# LCD.net
KiCad netlist of a schematic drawn in Altium Designer
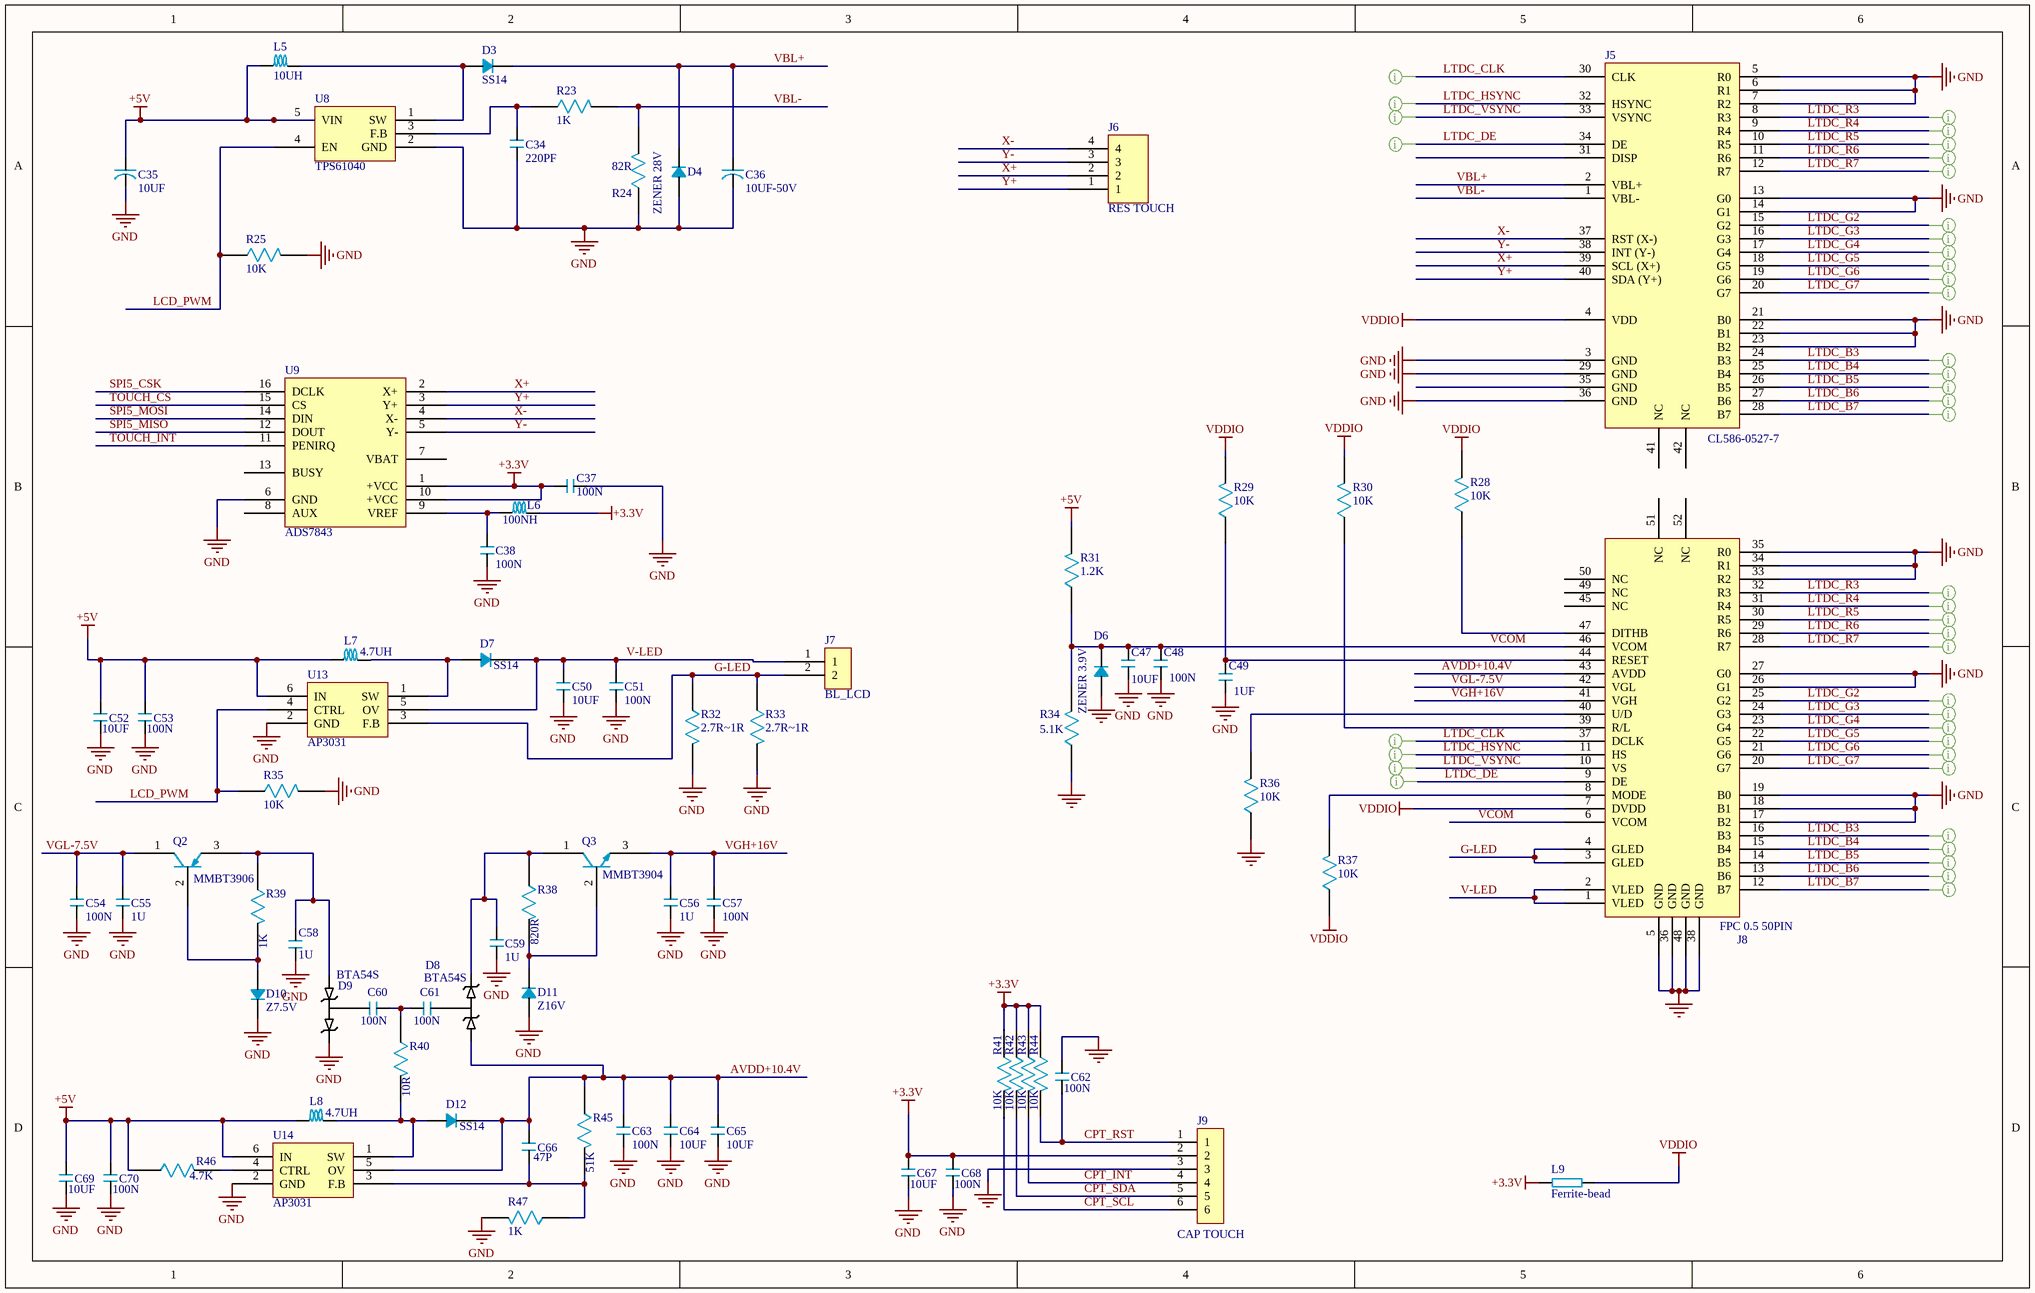
[diagram p0: LCD.SchDoc]

(export (version "E")
  (design (tool "Eeschema 10.0.6"))
  (components
    (comp (ref "C34") (value "220PF") (footprint "1206") (libsource (lib "R_L_C_V") (part "CAP")))
    (comp (ref "C35") (value "10UF") (footprint "1206") (libsource (lib "R_L_C_V") (part "CAP_POL")))
    (comp (ref "C36") (value "10UF-50V") (footprint "RB.1/.3") (libsource (lib "R_L_C_V") (part "CAP_POL")))
    (comp (ref "C37") (value "100N") (footprint "0603") (libsource (lib "R_L_C_V") (part "CAP")))
    (comp (ref "C38") (value "100N") (footprint "0603") (libsource (lib "R_L_C_V") (part "CAP")))
    (comp (ref "C47") (value "10UF") (footprint "0603") (libsource (lib "R_L_C_V") (part "CAP")))
    (comp (ref "C48") (value "100N") (footprint "0603") (libsource (lib "R_L_C_V") (part "CAP")))
    (comp (ref "C49") (value "1UF") (footprint "0603") (libsource (lib "R_L_C_V") (part "CAP")))
    (comp (ref "C50") (value "10UF") (footprint "0603") (libsource (lib "R_L_C_V") (part "CAP")))
    (comp (ref "C51") (value "100N") (footprint "0603") (libsource (lib "R_L_C_V") (part "CAP")))
    (comp (ref "C52") (value "10UF") (footprint "0603") (libsource (lib "R_L_C_V") (part "CAP")))
    (comp (ref "C53") (value "100N") (footprint "0603") (libsource (lib "R_L_C_V") (part "CAP")))
    (comp (ref "C54") (value "100N") (footprint "0603") (libsource (lib "R_L_C_V") (part "CAP")))
    (comp (ref "C55") (value "1U") (footprint "0603") (libsource (lib "R_L_C_V") (part "CAP")))
    (comp (ref "C56") (value "1U") (footprint "0603") (libsource (lib "R_L_C_V") (part "CAP")))
    (comp (ref "C57") (value "100N") (footprint "0603") (libsource (lib "R_L_C_V") (part "CAP")))
    (comp (ref "C58") (value "1U") (footprint "0603") (libsource (lib "R_L_C_V") (part "CAP")))
    (comp (ref "C59") (value "1U") (footprint "0603") (libsource (lib "R_L_C_V") (part "CAP")))
    (comp (ref "C60") (value "100N") (footprint "0603") (libsource (lib "R_L_C_V") (part "CAP")))
    (comp (ref "C61") (value "100N") (footprint "0603") (libsource (lib "R_L_C_V") (part "CAP")))
    (comp (ref "C62") (value "100N") (footprint "0603") (libsource (lib "R_L_C_V") (part "CAP")))
    (comp (ref "C63") (value "100N") (footprint "0603") (libsource (lib "R_L_C_V") (part "CAP")))
    (comp (ref "C64") (value "10UF") (footprint "0603") (libsource (lib "R_L_C_V") (part "CAP")))
    (comp (ref "C65") (value "10UF") (footprint "0603") (libsource (lib "R_L_C_V") (part "CAP")))
    (comp (ref "C66") (value "47P") (footprint "0603") (libsource (lib "R_L_C_V") (part "CAP")))
    (comp (ref "C67") (value "10UF") (footprint "0603") (libsource (lib "R_L_C_V") (part "CAP")))
    (comp (ref "C68") (value "100N") (footprint "0603") (libsource (lib "R_L_C_V") (part "CAP")))
    (comp (ref "C69") (value "10UF") (footprint "0603") (libsource (lib "R_L_C_V") (part "CAP")))
    (comp (ref "C70") (value "100N") (footprint "0603") (libsource (lib "R_L_C_V") (part "CAP")))
    (comp (ref "D3") (value "SS14") (footprint "SOD-123-B") (libsource (lib "R_L_C_V") (part "DIODE")))
    (comp (ref "D4") (value "ZENER 28V") (footprint "SOD-123") (libsource (lib "R_L_C_V") (part "DIODE")))
    (comp (ref "D6") (value "ZENER 3.9V") (footprint "SOD-123") (libsource (lib "R_L_C_V") (part "DIODE")))
    (comp (ref "D7") (value "SS14") (footprint "SOD-123-B") (libsource (lib "R_L_C_V") (part "DIODE")))
    (comp (ref "D8") (value "BTA54S") (footprint "SOT-23") (libsource (lib "MY_IC") (part "BTA54S")))
    (comp (ref "D9") (value "BTA54S") (footprint "SOT-23") (libsource (lib "MY_IC") (part "BTA54S")))
    (comp (ref "D10") (value "Z7.5V") (footprint "MINI-MELF") (libsource (lib "R_L_C_V") (part "DIODE")))
    (comp (ref "D11") (value "Z16V") (footprint "MINI-MELF") (libsource (lib "R_L_C_V") (part "DIODE")))
    (comp (ref "D12") (value "SS14") (footprint "SOD-123-B") (libsource (lib "R_L_C_V") (part "DIODE")))
    (comp (ref "J5")
      (value "CL586-0527-7")
      (footprint "PFC-40")
      (libsource (lib "CONNECTOR") (part "FPC 0.5 40PIN"))
    )
    (comp (ref "J6")
      (value "RES TOUCH")
      (footprint "4PIN-1.5MM-SMD")
      (libsource (lib "CONNECTOR") (part "4-PIN"))
    )
    (comp (ref "J7") (value "BL_LCD") (footprint "BL_LCD") (libsource (lib "CONNECTOR") (part "BL_LCD")))
    (comp (ref "J8")
      (value "FPC 0.5 50PIN")
      (footprint "PFC-50")
      (libsource (lib "CONNECTOR") (part "FPC 0.5 50PIN"))
    )
    (comp (ref "J9")
      (value "CAP TOUCH")
      (footprint "FPC-6-TOP-1MM")
      (description "FPC-6-TOP-1MM")
      (libsource (lib "CONNECTOR") (part "FPC-6-TOP-1MM"))
    )
    (comp (ref "L5") (value "10UH") (footprint "SELF_7MM") (libsource (lib "R_L_C_V") (part "SELF")))
    (comp (ref "L6") (value "100NH") (footprint "1206") (libsource (lib "R_L_C_V") (part "SELF")))
    (comp (ref "L7") (value "4.7UH") (footprint "SELF_7MM") (libsource (lib "R_L_C_V") (part "SELF")))
    (comp (ref "L8") (value "4.7UH") (footprint "SELF_7MM") (libsource (lib "") (part "SELF_1")))
    (comp (ref "L9")
      (value "Ferrite-bead")
      (footprint "0805")
      (libsource (lib "My_lib") (part "Ferrite-bead"))
    )
    (comp (ref "Q2") (value "MMBT3906") (footprint "BC337") (libsource (lib "TRANSISTORS") (part "PNP-SMD")))
    (comp (ref "Q3") (value "MMBT3904") (footprint "BC337") (libsource (lib "TRANSISTORS") (part "NPN-SMD")))
    (comp (ref "R23")
      (value "1K")
      (footprint "1206")
      (description "RES")
      (libsource (lib "R_L_C_V") (part "RES"))
    )
    (comp (ref "R24")
      (value "82R")
      (footprint "1206")
      (description "RES")
      (libsource (lib "R_L_C_V") (part "RES"))
    )
    (comp (ref "R25")
      (value "10K")
      (footprint "1206")
      (description "RES")
      (libsource (lib "R_L_C_V") (part "RES"))
    )
    (comp (ref "R28")
      (value "10K")
      (footprint "0603")
      (description "RES")
      (libsource (lib "R_L_C_V") (part "RES"))
    )
    (comp (ref "R29")
      (value "10K")
      (footprint "0603")
      (description "RES")
      (libsource (lib "R_L_C_V") (part "RES"))
    )
    (comp (ref "R30")
      (value "10K")
      (footprint "0603")
      (description "RES")
      (libsource (lib "R_L_C_V") (part "RES"))
    )
    (comp (ref "R31")
      (value "1.2K")
      (footprint "0603")
      (description "RES")
      (libsource (lib "R_L_C_V") (part "RES"))
    )
    (comp (ref "R32")
      (value "2.7R~1R")
      (footprint "0603")
      (description "RES")
      (libsource (lib "R_L_C_V") (part "RES"))
    )
    (comp (ref "R33")
      (value "2.7R~1R")
      (footprint "0603")
      (description "RES")
      (libsource (lib "R_L_C_V") (part "RES"))
    )
    (comp (ref "R34")
      (value "5.1K")
      (footprint "0603")
      (description "RES")
      (libsource (lib "R_L_C_V") (part "RES"))
    )
    (comp (ref "R35")
      (value "10K")
      (footprint "0603")
      (description "RES")
      (libsource (lib "R_L_C_V") (part "RES"))
    )
    (comp (ref "R36")
      (value "10K")
      (footprint "0603")
      (description "RES")
      (libsource (lib "R_L_C_V") (part "RES"))
    )
    (comp (ref "R37")
      (value "10K")
      (footprint "0603")
      (description "RES")
      (libsource (lib "R_L_C_V") (part "RES"))
    )
    (comp (ref "R38")
      (value "820R")
      (footprint "0603")
      (description "RES")
      (libsource (lib "R_L_C_V") (part "RES"))
    )
    (comp (ref "R39")
      (value "1K")
      (footprint "0603")
      (description "RES")
      (libsource (lib "R_L_C_V") (part "RES"))
    )
    (comp (ref "R40")
      (value "10R")
      (footprint "0603")
      (description "RES")
      (libsource (lib "R_L_C_V") (part "RES"))
    )
    (comp (ref "R41")
      (value "10K")
      (footprint "0603")
      (description "RES")
      (libsource (lib "R_L_C_V") (part "RES"))
    )
    (comp (ref "R42")
      (value "10K")
      (footprint "0603")
      (description "RES")
      (libsource (lib "R_L_C_V") (part "RES"))
    )
    (comp (ref "R43")
      (value "10K")
      (footprint "0603")
      (description "RES")
      (libsource (lib "R_L_C_V") (part "RES"))
    )
    (comp (ref "R44")
      (value "10K")
      (footprint "0603")
      (description "RES")
      (libsource (lib "R_L_C_V") (part "RES"))
    )
    (comp (ref "R45")
      (value "51K")
      (footprint "0603")
      (description "RES")
      (libsource (lib "R_L_C_V") (part "RES"))
    )
    (comp (ref "R46")
      (value "4.7K")
      (footprint "0603")
      (description "RES")
      (libsource (lib "R_L_C_V") (part "RES"))
    )
    (comp (ref "R47")
      (value "1K")
      (footprint "0603")
      (description "RES")
      (libsource (lib "R_L_C_V") (part "RES"))
    )
    (comp (ref "U8") (value "TPS61040") (footprint "SOT23-5") (libsource (lib "MY_IC") (part "TPS61040")))
    (comp (ref "U9") (value "ADS7843") (footprint "TSSOP-16") (libsource (lib "MY_IC") (part "ADS7843")))
    (comp (ref "U13") (value "AP3031") (footprint "SOT23-6") (libsource (lib "MY_IC") (part "AP3031")))
    (comp (ref "U14") (value "AP3031") (footprint "SOT23-6") (libsource (lib "MY_IC") (part "AP3031")))
  )
  (nets
    (net (code "1") (name "+3.3V") (class "Default")
      (node (ref "C37") (pin "2") (pintype "passive"))
      (node (ref "C67") (pin "1") (pintype "passive"))
      (node (ref "C68") (pin "1") (pintype "passive"))
      (node (ref "J9") (pin "2") (pinfunction "2_2") (pintype "passive"))
      (node (ref "L6") (pin "2") (pintype "passive"))
      (node (ref "L9") (pin "1") (pintype "passive"))
      (node (ref "R41") (pin "1") (pintype "passive"))
      (node (ref "R42") (pin "1") (pintype "passive"))
      (node (ref "R43") (pin "1") (pintype "passive"))
      (node (ref "R44") (pin "1") (pintype "passive"))
      (node (ref "U9") (pin "1") (pinfunction "+VCC_1") (pintype "passive"))
      (node (ref "U9") (pin "10") (pinfunction "+VCC_10") (pintype "passive"))
    )
    (net (code "2") (name "+5V") (class "Default")
      (node (ref "C35") (pin "1") (pintype "passive"))
      (node (ref "C52") (pin "1") (pintype "passive"))
      (node (ref "C53") (pin "1") (pintype "passive"))
      (node (ref "C69") (pin "1") (pintype "passive"))
      (node (ref "C70") (pin "1") (pintype "passive"))
      (node (ref "L5") (pin "1") (pintype "passive"))
      (node (ref "L7") (pin "1") (pintype "passive"))
      (node (ref "L8") (pin "1") (pintype "passive"))
      (node (ref "R31") (pin "2") (pintype "passive"))
      (node (ref "R46") (pin "1") (pintype "passive"))
      (node (ref "U13") (pin "6") (pinfunction "IN_6") (pintype "passive"))
      (node (ref "U14") (pin "6") (pinfunction "IN_6") (pintype "passive"))
      (node (ref "U8") (pin "5") (pinfunction "VIN_5") (pintype "passive"))
    )
    (net (code "3") (name "/AVDD+10.4V") (class "Default")
      (node (ref "C63") (pin "1") (pintype "passive"))
      (node (ref "C64") (pin "1") (pintype "passive"))
      (node (ref "C65") (pin "1") (pintype "passive"))
      (node (ref "C66") (pin "1") (pintype "passive"))
      (node (ref "D12") (pin "2") (pintype "passive"))
      (node (ref "D8") (pin "1") (pinfunction "1_1") (pintype "passive"))
      (node (ref "J8") (pin "43") (pinfunction "AVDD_43") (pintype "passive"))
      (node (ref "R45") (pin "1") (pintype "passive"))
      (node (ref "U14") (pin "5") (pinfunction "OV_5") (pintype "passive"))
    )
    (net (code "4") (name "/CPT_INT") (class "Default")
      (node (ref "J9") (pin "4") (pinfunction "4_4") (pintype "passive"))
      (node (ref "R43") (pin "2") (pintype "passive"))
    )
    (net (code "5") (name "/CPT_RST") (class "Default")
      (node (ref "C62") (pin "2") (pintype "passive"))
      (node (ref "J9") (pin "1") (pinfunction "1_1") (pintype "passive"))
      (node (ref "R44") (pin "2") (pintype "passive"))
    )
    (net (code "6") (name "/CPT_SCL") (class "Default")
      (node (ref "J9") (pin "6") (pinfunction "6_6") (pintype "passive"))
      (node (ref "R41") (pin "2") (pintype "passive"))
    )
    (net (code "7") (name "/CPT_SDA") (class "Default")
      (node (ref "J9") (pin "5") (pinfunction "5_5") (pintype "passive"))
      (node (ref "R42") (pin "2") (pintype "passive"))
    )
    (net (code "8") (name "/G-LED") (class "Default")
      (node (ref "J7") (pin "2") (pinfunction "2_2") (pintype "passive"))
      (node (ref "J8") (pin "3") (pinfunction "GLED_3") (pintype "passive"))
      (node (ref "J8") (pin "4") (pinfunction "GLED_4") (pintype "passive"))
      (node (ref "R32") (pin "1") (pintype "passive"))
      (node (ref "R33") (pin "1") (pintype "passive"))
      (node (ref "U13") (pin "3") (pinfunction "F.B_3") (pintype "passive"))
    )
    (net (code "9") (name "/LCD_PWM") (class "Default")
      (node (ref "R25") (pin "1") (pintype "passive"))
      (node (ref "R35") (pin "1") (pintype "passive"))
      (node (ref "U13") (pin "4") (pinfunction "CTRL_4") (pintype "passive"))
      (node (ref "U8") (pin "4") (pinfunction "EN_4") (pintype "passive"))
    )
    (net (code "10") (name "/LTDC_B3") (class "Default")
      (node (ref "J5") (pin "24") (pinfunction "B3_24") (pintype "passive"))
      (node (ref "J8") (pin "16") (pinfunction "B3_16") (pintype "passive"))
    )
    (net (code "11") (name "/LTDC_B4") (class "Default")
      (node (ref "J5") (pin "25") (pinfunction "B4_25") (pintype "passive"))
      (node (ref "J8") (pin "15") (pinfunction "B4_15") (pintype "passive"))
    )
    (net (code "12") (name "/LTDC_B5") (class "Default")
      (node (ref "J5") (pin "26") (pinfunction "B5_26") (pintype "passive"))
      (node (ref "J8") (pin "14") (pinfunction "B5_14") (pintype "passive"))
    )
    (net (code "13") (name "/LTDC_B6") (class "Default")
      (node (ref "J5") (pin "27") (pinfunction "B6_27") (pintype "passive"))
      (node (ref "J8") (pin "13") (pinfunction "B6_13") (pintype "passive"))
    )
    (net (code "14") (name "/LTDC_B7") (class "Default")
      (node (ref "J5") (pin "28") (pinfunction "B7_28") (pintype "passive"))
      (node (ref "J8") (pin "12") (pinfunction "B7_12") (pintype "passive"))
    )
    (net (code "15") (name "/LTDC_CLK") (class "Default")
      (node (ref "J5") (pin "30") (pinfunction "CLK_30") (pintype "passive"))
      (node (ref "J8") (pin "37") (pinfunction "DCLK_37") (pintype "passive"))
    )
    (net (code "16") (name "/LTDC_DE") (class "Default")
      (node (ref "J5") (pin "34") (pinfunction "DE_34") (pintype "passive"))
      (node (ref "J8") (pin "9") (pinfunction "DE_9") (pintype "passive"))
    )
    (net (code "17") (name "/LTDC_G2") (class "Default")
      (node (ref "J5") (pin "15") (pinfunction "G2_15") (pintype "passive"))
      (node (ref "J8") (pin "25") (pinfunction "G2_25") (pintype "passive"))
    )
    (net (code "18") (name "/LTDC_G3") (class "Default")
      (node (ref "J5") (pin "16") (pinfunction "G3_16") (pintype "passive"))
      (node (ref "J8") (pin "24") (pinfunction "G3_24") (pintype "passive"))
    )
    (net (code "19") (name "/LTDC_G4") (class "Default")
      (node (ref "J5") (pin "17") (pinfunction "G4_17") (pintype "passive"))
      (node (ref "J8") (pin "23") (pinfunction "G4_23") (pintype "passive"))
    )
    (net (code "20") (name "/LTDC_G5") (class "Default")
      (node (ref "J5") (pin "18") (pinfunction "G5_18") (pintype "passive"))
      (node (ref "J8") (pin "22") (pinfunction "G5_22") (pintype "passive"))
    )
    (net (code "21") (name "/LTDC_G6") (class "Default")
      (node (ref "J5") (pin "19") (pinfunction "G6_19") (pintype "passive"))
      (node (ref "J8") (pin "21") (pinfunction "G6_21") (pintype "passive"))
    )
    (net (code "22") (name "/LTDC_G7") (class "Default")
      (node (ref "J5") (pin "20") (pinfunction "G7_20") (pintype "passive"))
      (node (ref "J8") (pin "20") (pinfunction "G7_20") (pintype "passive"))
    )
    (net (code "23") (name "/LTDC_HSYNC") (class "Default")
      (node (ref "J5") (pin "32") (pinfunction "HSYNC_32") (pintype "passive"))
      (node (ref "J8") (pin "11") (pinfunction "HS_11") (pintype "passive"))
    )
    (net (code "24") (name "/LTDC_R3") (class "Default")
      (node (ref "J5") (pin "8") (pinfunction "R3_8") (pintype "passive"))
      (node (ref "J8") (pin "32") (pinfunction "R3_32") (pintype "passive"))
    )
    (net (code "25") (name "/LTDC_R4") (class "Default")
      (node (ref "J5") (pin "9") (pinfunction "R4_9") (pintype "passive"))
      (node (ref "J8") (pin "31") (pinfunction "R4_31") (pintype "passive"))
    )
    (net (code "26") (name "/LTDC_R5") (class "Default")
      (node (ref "J5") (pin "10") (pinfunction "R5_10") (pintype "passive"))
      (node (ref "J8") (pin "30") (pinfunction "R5_30") (pintype "passive"))
    )
    (net (code "27") (name "/LTDC_R6") (class "Default")
      (node (ref "J5") (pin "11") (pinfunction "R6_11") (pintype "passive"))
      (node (ref "J8") (pin "29") (pinfunction "R6_29") (pintype "passive"))
    )
    (net (code "28") (name "/LTDC_R7") (class "Default")
      (node (ref "J5") (pin "12") (pinfunction "R7_12") (pintype "passive"))
      (node (ref "J8") (pin "28") (pinfunction "R7_28") (pintype "passive"))
    )
    (net (code "29") (name "/LTDC_VSYNC") (class "Default")
      (node (ref "J5") (pin "33") (pinfunction "VSYNC_33") (pintype "passive"))
      (node (ref "J8") (pin "10") (pinfunction "VS_10") (pintype "passive"))
    )
    (net (code "30") (name "/SPI5_CSK") (class "Default")
      (node (ref "U9") (pin "16") (pinfunction "DCLK_16") (pintype "passive"))
    )
    (net (code "31") (name "/SPI5_MISO") (class "Default")
      (node (ref "U9") (pin "12") (pinfunction "DOUT_12") (pintype "passive"))
    )
    (net (code "32") (name "/SPI5_MOSI") (class "Default")
      (node (ref "U9") (pin "14") (pinfunction "DIN_14") (pintype "passive"))
    )
    (net (code "33") (name "/TOUCH_CS") (class "Default")
      (node (ref "U9") (pin "15") (pinfunction "CS_15") (pintype "passive"))
    )
    (net (code "34") (name "/TOUCH_INT") (class "Default")
      (node (ref "U9") (pin "11") (pinfunction "PENIRQ_11") (pintype "passive"))
    )
    (net (code "35") (name "/V-LED") (class "Default")
      (node (ref "C50") (pin "1") (pintype "passive"))
      (node (ref "C51") (pin "1") (pintype "passive"))
      (node (ref "D7") (pin "2") (pintype "passive"))
      (node (ref "J7") (pin "1") (pinfunction "1_1") (pintype "passive"))
      (node (ref "J8") (pin "1") (pinfunction "VLED_1") (pintype "passive"))
      (node (ref "J8") (pin "2") (pinfunction "VLED_2") (pintype "passive"))
      (node (ref "U13") (pin "5") (pinfunction "OV_5") (pintype "passive"))
    )
    (net (code "36") (name "/VBL+") (class "Default")
      (node (ref "C36") (pin "1") (pintype "passive"))
      (node (ref "D3") (pin "2") (pintype "passive"))
      (node (ref "D4") (pin "2") (pintype "passive"))
      (node (ref "J5") (pin "2") (pinfunction "VBL+_2") (pintype "passive"))
    )
    (net (code "37") (name "/VBL-") (class "Default")
      (node (ref "J5") (pin "1") (pinfunction "VBL-_1") (pintype "passive"))
      (node (ref "R23") (pin "2") (pintype "passive"))
      (node (ref "R24") (pin "2") (pintype "passive"))
    )
    (net (code "38") (name "/VCOM") (class "Default")
      (node (ref "C47") (pin "1") (pintype "passive"))
      (node (ref "C48") (pin "1") (pintype "passive"))
      (node (ref "D6") (pin "2") (pintype "passive"))
      (node (ref "J8") (pin "46") (pinfunction "VCOM_46") (pintype "passive"))
      (node (ref "J8") (pin "6") (pinfunction "VCOM_6") (pintype "passive"))
      (node (ref "R31") (pin "1") (pintype "passive"))
      (node (ref "R34") (pin "2") (pintype "passive"))
    )
    (net (code "39") (name "/VGH+16V") (class "Default")
      (node (ref "C56") (pin "1") (pintype "passive"))
      (node (ref "C57") (pin "1") (pintype "passive"))
      (node (ref "J8") (pin "41") (pinfunction "VGH_41") (pintype "passive"))
      (node (ref "Q3") (pin "3") (pintype "passive"))
    )
    (net (code "40") (name "/VGL-7.5V") (class "Default")
      (node (ref "C54") (pin "1") (pintype "passive"))
      (node (ref "C55") (pin "1") (pintype "passive"))
      (node (ref "J8") (pin "42") (pinfunction "VGL_42") (pintype "passive"))
      (node (ref "Q2") (pin "1") (pintype "passive"))
    )
    (net (code "41") (name "/X+") (class "Default")
      (node (ref "J5") (pin "39") (pinfunction "SCL_(X+)_39") (pintype "passive"))
      (node (ref "J6") (pin "2") (pinfunction "2_2") (pintype "passive"))
      (node (ref "U9") (pin "2") (pinfunction "X+_2") (pintype "passive"))
    )
    (net (code "42") (name "/X-") (class "Default")
      (node (ref "J5") (pin "37") (pinfunction "RST_(X-)_37") (pintype "passive"))
      (node (ref "J6") (pin "4") (pinfunction "4_4") (pintype "passive"))
      (node (ref "U9") (pin "4") (pinfunction "X-_4") (pintype "passive"))
    )
    (net (code "43") (name "/Y+") (class "Default")
      (node (ref "J5") (pin "40") (pinfunction "SDA_(Y+)_40") (pintype "passive"))
      (node (ref "J6") (pin "1") (pinfunction "1_1") (pintype "passive"))
      (node (ref "U9") (pin "3") (pinfunction "Y+_3") (pintype "passive"))
    )
    (net (code "44") (name "/Y-") (class "Default")
      (node (ref "J5") (pin "38") (pinfunction "INT_(Y-)_38") (pintype "passive"))
      (node (ref "J6") (pin "3") (pinfunction "3_3") (pintype "passive"))
      (node (ref "U9") (pin "5") (pinfunction "Y-_5") (pintype "passive"))
    )
    (net (code "45") (name "GND") (class "Default")
      (node (ref "C34") (pin "1") (pintype "passive"))
      (node (ref "C35") (pin "2") (pintype "passive"))
      (node (ref "C36") (pin "2") (pintype "passive"))
      (node (ref "C37") (pin "1") (pintype "passive"))
      (node (ref "C38") (pin "1") (pintype "passive"))
      (node (ref "C47") (pin "2") (pintype "passive"))
      (node (ref "C48") (pin "2") (pintype "passive"))
      (node (ref "C49") (pin "2") (pintype "passive"))
      (node (ref "C50") (pin "2") (pintype "passive"))
      (node (ref "C51") (pin "2") (pintype "passive"))
      (node (ref "C52") (pin "2") (pintype "passive"))
      (node (ref "C53") (pin "2") (pintype "passive"))
      (node (ref "C54") (pin "2") (pintype "passive"))
      (node (ref "C55") (pin "2") (pintype "passive"))
      (node (ref "C56") (pin "2") (pintype "passive"))
      (node (ref "C57") (pin "2") (pintype "passive"))
      (node (ref "C58") (pin "2") (pintype "passive"))
      (node (ref "C59") (pin "2") (pintype "passive"))
      (node (ref "C62") (pin "1") (pintype "passive"))
      (node (ref "C63") (pin "2") (pintype "passive"))
      (node (ref "C64") (pin "2") (pintype "passive"))
      (node (ref "C65") (pin "2") (pintype "passive"))
      (node (ref "C67") (pin "2") (pintype "passive"))
      (node (ref "C68") (pin "2") (pintype "passive"))
      (node (ref "C69") (pin "2") (pintype "passive"))
      (node (ref "C70") (pin "2") (pintype "passive"))
      (node (ref "D10") (pin "2") (pintype "passive"))
      (node (ref "D11") (pin "1") (pintype "passive"))
      (node (ref "D4") (pin "1") (pintype "passive"))
      (node (ref "D6") (pin "1") (pintype "passive"))
      (node (ref "D9") (pin "2") (pinfunction "2_2") (pintype "passive"))
      (node (ref "J5") (pin "13") (pinfunction "G0_13") (pintype "passive"))
      (node (ref "J5") (pin "14") (pinfunction "G1_14") (pintype "passive"))
      (node (ref "J5") (pin "21") (pinfunction "B0_21") (pintype "passive"))
      (node (ref "J5") (pin "22") (pinfunction "B1_22") (pintype "passive"))
      (node (ref "J5") (pin "23") (pinfunction "B2_23") (pintype "passive"))
      (node (ref "J5") (pin "29") (pinfunction "GND_29") (pintype "passive"))
      (node (ref "J5") (pin "3") (pinfunction "GND_3") (pintype "passive"))
      (node (ref "J5") (pin "36") (pinfunction "GND_36") (pintype "passive"))
      (node (ref "J5") (pin "5") (pinfunction "R0_5") (pintype "passive"))
      (node (ref "J5") (pin "6") (pinfunction "R1_6") (pintype "passive"))
      (node (ref "J5") (pin "7") (pinfunction "R2_7") (pintype "passive"))
      (node (ref "J8") (pin "17") (pinfunction "B2_17") (pintype "passive"))
      (node (ref "J8") (pin "18") (pinfunction "B1_18") (pintype "passive"))
      (node (ref "J8") (pin "19") (pinfunction "B0_19") (pintype "passive"))
      (node (ref "J8") (pin "26") (pinfunction "G1_26") (pintype "passive"))
      (node (ref "J8") (pin "27") (pinfunction "G0_27") (pintype "passive"))
      (node (ref "J8") (pin "33") (pinfunction "R2_33") (pintype "passive"))
      (node (ref "J8") (pin "34") (pinfunction "R1_34") (pintype "passive"))
      (node (ref "J8") (pin "35") (pinfunction "R0_35") (pintype "passive"))
      (node (ref "J8") (pin "36") (pinfunction "GND_36") (pintype "passive"))
      (node (ref "J8") (pin "38") (pinfunction "GND_38") (pintype "passive"))
      (node (ref "J8") (pin "48") (pinfunction "GND_48") (pintype "passive"))
      (node (ref "J8") (pin "5") (pinfunction "GND_5") (pintype "passive"))
      (node (ref "J9") (pin "3") (pinfunction "3_3") (pintype "passive"))
      (node (ref "R24") (pin "1") (pintype "passive"))
      (node (ref "R25") (pin "2") (pintype "passive"))
      (node (ref "R32") (pin "2") (pintype "passive"))
      (node (ref "R33") (pin "2") (pintype "passive"))
      (node (ref "R34") (pin "1") (pintype "passive"))
      (node (ref "R35") (pin "2") (pintype "passive"))
      (node (ref "R36") (pin "1") (pintype "passive"))
      (node (ref "R47") (pin "2") (pintype "passive"))
      (node (ref "U13") (pin "2") (pinfunction "GND_2") (pintype "passive"))
      (node (ref "U14") (pin "2") (pinfunction "GND_2") (pintype "passive"))
      (node (ref "U8") (pin "2") (pinfunction "GND_2") (pintype "passive"))
      (node (ref "U9") (pin "6") (pinfunction "GND_6") (pintype "passive"))
    )
    (net (code "46") (name "Net-(C58-Pad1)") (class "Default")
      (node (ref "C58") (pin "1") (pintype "passive"))
      (node (ref "D9") (pin "1") (pinfunction "1_1") (pintype "passive"))
      (node (ref "Q2") (pin "3") (pintype "passive"))
      (node (ref "R39") (pin "1") (pintype "passive"))
    )
    (net (code "47") (name "Net-(C59-Pad1)") (class "Default")
      (node (ref "C59") (pin "1") (pintype "passive"))
      (node (ref "D8") (pin "2") (pinfunction "2_2") (pintype "passive"))
      (node (ref "Q3") (pin "1") (pintype "passive"))
      (node (ref "R38") (pin "1") (pintype "passive"))
    )
    (net (code "48") (name "Net-(C60-Pad1)") (class "Default")
      (node (ref "C60") (pin "1") (pintype "passive"))
      (node (ref "D9") (pin "3") (pinfunction "3_3") (pintype "passive"))
    )
    (net (code "49") (name "Net-(C60-Pad2)") (class "Default")
      (node (ref "C60") (pin "2") (pintype "passive"))
      (node (ref "C61") (pin "1") (pintype "passive"))
      (node (ref "R40") (pin "1") (pintype "passive"))
    )
    (net (code "50") (name "Net-(C61-Pad2)") (class "Default")
      (node (ref "C61") (pin "2") (pintype "passive"))
      (node (ref "D8") (pin "3") (pinfunction "3_3") (pintype "passive"))
    )
    (net (code "51") (name "Net-(D10-Pad1)") (class "Default")
      (node (ref "D10") (pin "1") (pintype "passive"))
      (node (ref "Q2") (pin "2") (pintype "passive"))
      (node (ref "R39") (pin "2") (pintype "passive"))
    )
    (net (code "52") (name "Net-(D11-Pad2)") (class "Default")
      (node (ref "D11") (pin "2") (pintype "passive"))
      (node (ref "Q3") (pin "2") (pintype "passive"))
      (node (ref "R38") (pin "2") (pintype "passive"))
    )
    (net (code "53") (name "Net-(J8-DITHB)") (class "Default")
      (node (ref "J8") (pin "47") (pinfunction "DITHB_47") (pintype "passive"))
      (node (ref "R28") (pin "1") (pintype "passive"))
    )
    (net (code "54") (name "Net-(J8-MODE)") (class "Default")
      (node (ref "J8") (pin "8") (pinfunction "MODE_8") (pintype "passive"))
      (node (ref "R37") (pin "2") (pintype "passive"))
    )
    (net (code "55") (name "Net-(J8-RESET)") (class "Default")
      (node (ref "C49") (pin "1") (pintype "passive"))
      (node (ref "J8") (pin "44") (pinfunction "RESET_44") (pintype "passive"))
      (node (ref "R29") (pin "1") (pintype "passive"))
    )
    (net (code "56") (name "Net-(J8-R{slash}L)") (class "Default")
      (node (ref "J8") (pin "39") (pinfunction "R/L_39") (pintype "passive"))
      (node (ref "R30") (pin "1") (pintype "passive"))
    )
    (net (code "57") (name "Net-(J8-U{slash}D)") (class "Default")
      (node (ref "J8") (pin "40") (pinfunction "U/D_40") (pintype "passive"))
      (node (ref "R36") (pin "2") (pintype "passive"))
    )
    (net (code "58") (name "Net-(U8-F.B)") (class "Default")
      (node (ref "C34") (pin "2") (pintype "passive"))
      (node (ref "R23") (pin "1") (pintype "passive"))
      (node (ref "U8") (pin "3") (pinfunction "F.B_3") (pintype "passive"))
    )
    (net (code "59") (name "Net-(U8-SW)") (class "Default")
      (node (ref "D3") (pin "1") (pintype "passive"))
      (node (ref "L5") (pin "2") (pintype "passive"))
      (node (ref "U8") (pin "1") (pinfunction "SW_1") (pintype "passive"))
    )
    (net (code "60") (name "Net-(U9-VREF)") (class "Default")
      (node (ref "C38") (pin "2") (pintype "passive"))
      (node (ref "L6") (pin "1") (pintype "passive"))
      (node (ref "U9") (pin "9") (pinfunction "VREF_9") (pintype "passive"))
    )
    (net (code "61") (name "Net-(U13-SW)") (class "Default")
      (node (ref "D7") (pin "1") (pintype "passive"))
      (node (ref "L7") (pin "2") (pintype "passive"))
      (node (ref "U13") (pin "1") (pinfunction "SW_1") (pintype "passive"))
    )
    (net (code "62") (name "Net-(U14-CTRL)") (class "Default")
      (node (ref "R46") (pin "2") (pintype "passive"))
      (node (ref "U14") (pin "4") (pinfunction "CTRL_4") (pintype "passive"))
    )
    (net (code "63") (name "Net-(U14-F.B)") (class "Default")
      (node (ref "C66") (pin "2") (pintype "passive"))
      (node (ref "R45") (pin "2") (pintype "passive"))
      (node (ref "R47") (pin "1") (pintype "passive"))
      (node (ref "U14") (pin "3") (pinfunction "F.B_3") (pintype "passive"))
    )
    (net (code "64") (name "Net-(U14-SW)") (class "Default")
      (node (ref "D12") (pin "1") (pintype "passive"))
      (node (ref "L8") (pin "2") (pintype "passive"))
      (node (ref "R40") (pin "2") (pintype "passive"))
      (node (ref "U14") (pin "1") (pinfunction "SW_1") (pintype "passive"))
    )
    (net (code "65") (name "VDDIO") (class "Default")
      (node (ref "J5") (pin "4") (pinfunction "VDD_4") (pintype "passive"))
      (node (ref "J8") (pin "7") (pinfunction "DVDD_7") (pintype "passive"))
      (node (ref "L9") (pin "2") (pintype "passive"))
      (node (ref "R28") (pin "2") (pintype "passive"))
      (node (ref "R29") (pin "2") (pintype "passive"))
      (node (ref "R30") (pin "2") (pintype "passive"))
      (node (ref "R37") (pin "1") (pintype "passive"))
    )
    (net (code "66") (name "unconnected-(J5-DISP-Pad31)") (class "Default")
      (node (ref "J5") (pin "31") (pinfunction "DISP_31") (pintype "passive"))
    )
    (net (code "67") (name "unconnected-(J5-GND-Pad35)") (class "Default")
      (node (ref "J5") (pin "35") (pinfunction "GND_35") (pintype "passive"))
    )
    (net (code "68") (name "unconnected-(J5-NC-Pad41)") (class "Default")
      (node (ref "J5") (pin "41") (pinfunction "NC_41") (pintype "passive"))
    )
    (net (code "69") (name "unconnected-(J5-NC-Pad42)") (class "Default")
      (node (ref "J5") (pin "42") (pinfunction "NC_42") (pintype "passive"))
    )
    (net (code "70") (name "unconnected-(J8-NC-Pad45)") (class "Default")
      (node (ref "J8") (pin "45") (pinfunction "NC_45") (pintype "passive"))
    )
    (net (code "71") (name "unconnected-(J8-NC-Pad49)") (class "Default")
      (node (ref "J8") (pin "49") (pinfunction "NC_49") (pintype "passive"))
    )
    (net (code "72") (name "unconnected-(J8-NC-Pad50)") (class "Default")
      (node (ref "J8") (pin "50") (pinfunction "NC_50") (pintype "passive"))
    )
    (net (code "73") (name "unconnected-(J8-NC-Pad51)") (class "Default")
      (node (ref "J8") (pin "51") (pinfunction "NC_51") (pintype "passive"))
    )
    (net (code "74") (name "unconnected-(J8-NC-Pad52)") (class "Default")
      (node (ref "J8") (pin "52") (pinfunction "NC_52") (pintype "passive"))
    )
    (net (code "75") (name "unconnected-(U9-AUX-Pad8)") (class "Default")
      (node (ref "U9") (pin "8") (pinfunction "AUX_8") (pintype "passive"))
    )
    (net (code "76") (name "unconnected-(U9-BUSY-Pad13)") (class "Default")
      (node (ref "U9") (pin "13") (pinfunction "BUSY_13") (pintype "passive"))
    )
    (net (code "77") (name "unconnected-(U9-VBAT-Pad7)") (class "Default")
      (node (ref "U9") (pin "7") (pinfunction "VBAT_7") (pintype "passive"))
    )
  )
)
